# RM1xx-Breakout-min.net
KiCad netlist of a schematic drawn in EAGLE
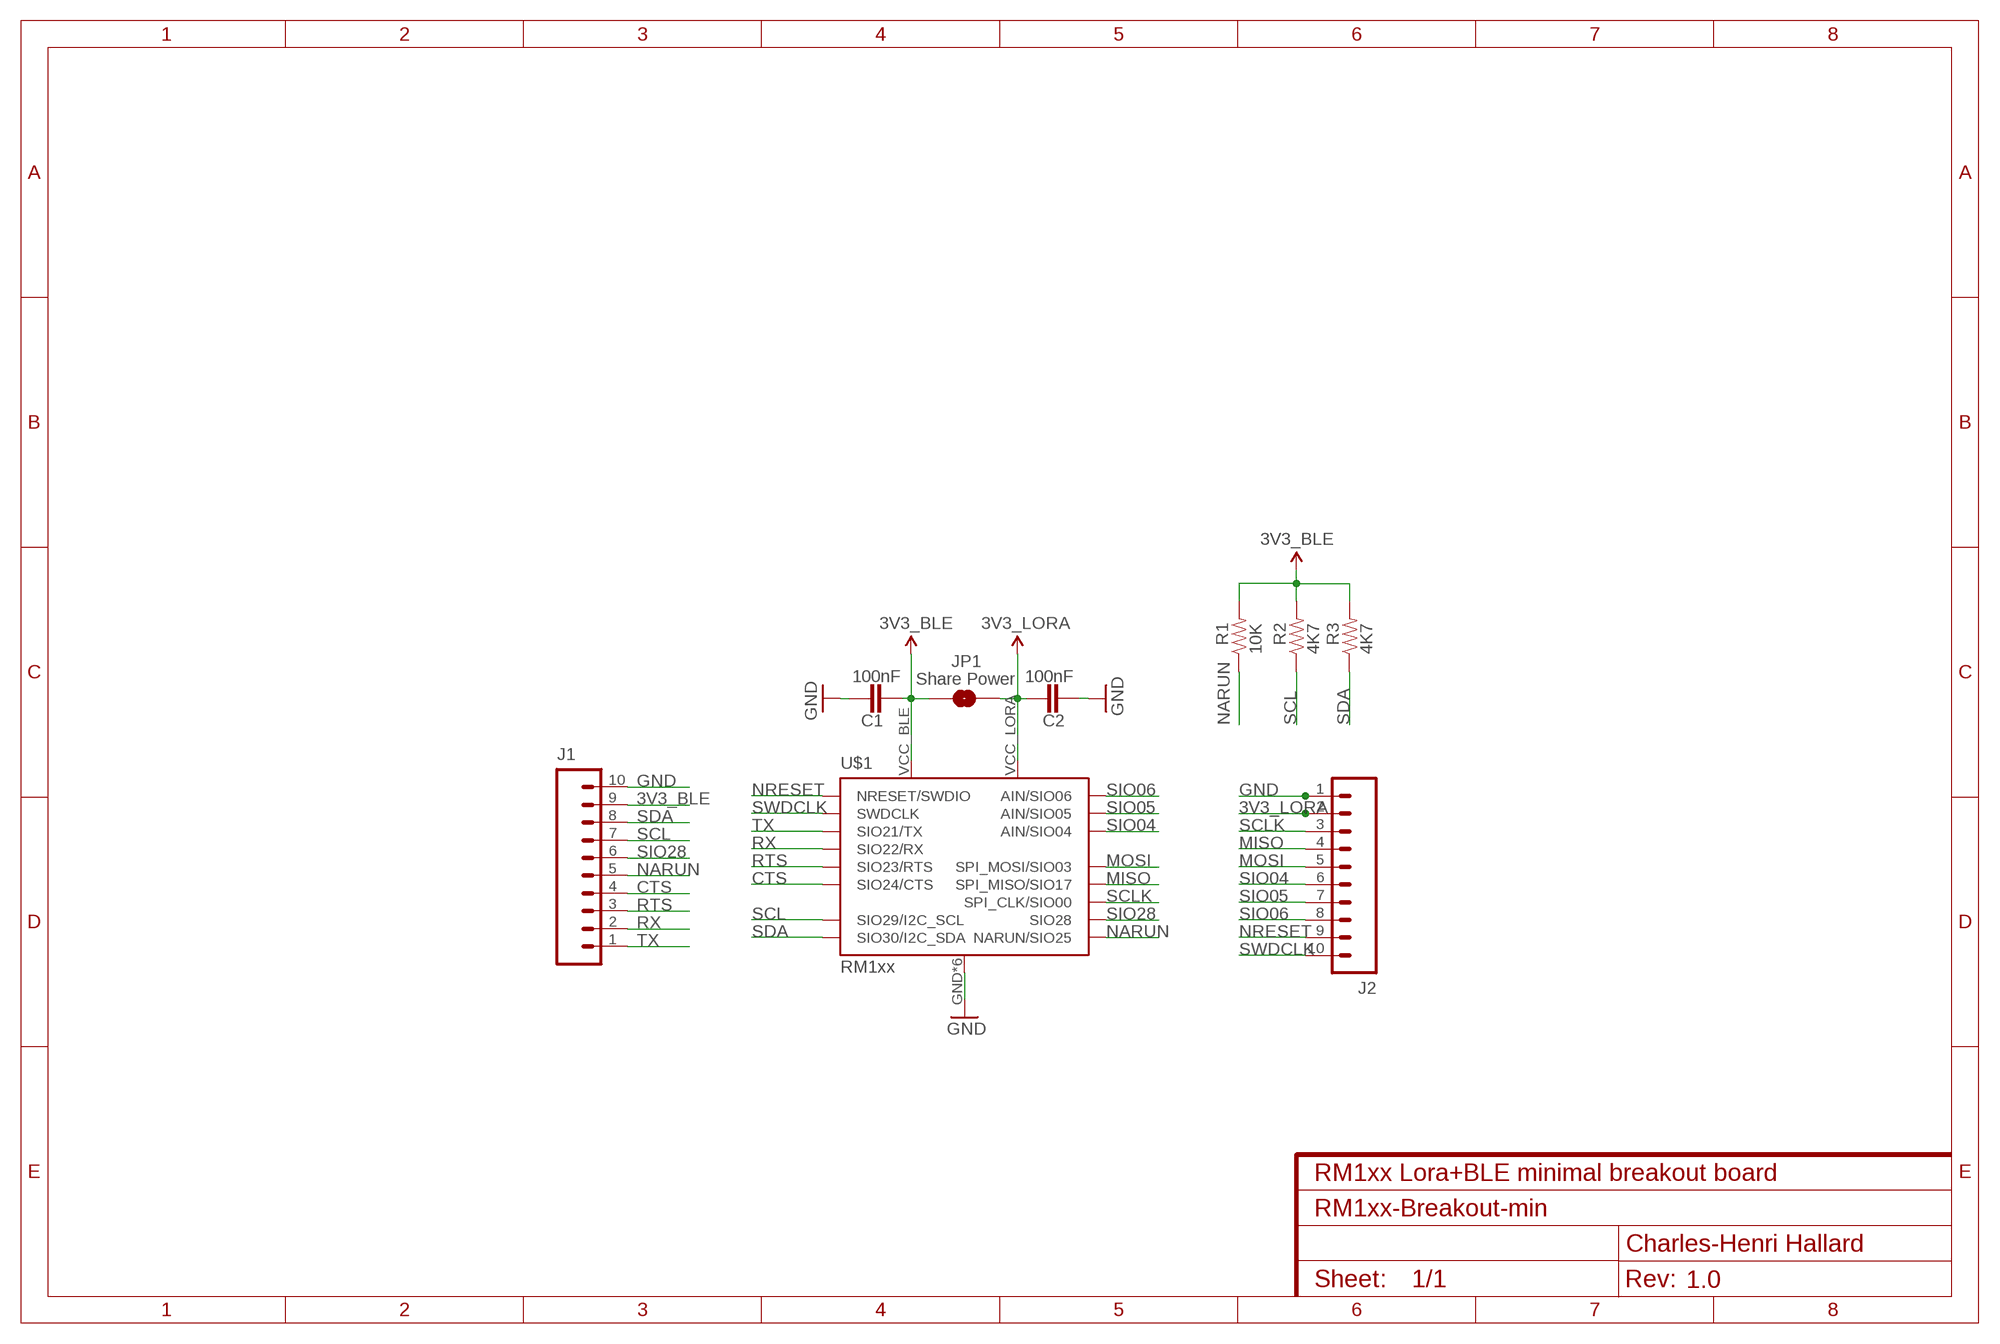
[diagram p0: schematic, sheet 1]

(export (version "E")
  (design (tool "Eeschema 10.0.6"))
  (components
    (comp (ref "C1")
      (value "100nF")
      (footprint "eagle-import:0805-CAP")
      (libsource (lib "eagle-import") (part "CAP0805-CAP"))
    )
    (comp (ref "C2")
      (value "100nF")
      (footprint "eagle-import:0805-CAP")
      (libsource (lib "eagle-import") (part "CAP0805-CAP"))
    )
    (comp (ref "J1")
      (value "M10LOCK")
      (footprint "eagle-import:1X10_LOCK")
      (libsource (lib "eagle-import") (part "M10LOCK"))
    )
    (comp (ref "J2")
      (value "M10LOCK")
      (footprint "eagle-import:1X10_LOCK")
      (libsource (lib "eagle-import") (part "M10LOCK"))
    )
    (comp (ref "JP1")
      (value "Share Power")
      (footprint "eagle-import:PAD-JUMPER-2-NO_YES_SILK")
      (libsource (lib "eagle-import") (part "JUMPER-PAD-2-NOYES_SILK"))
    )
    (comp (ref "R1")
      (value "10K")
      (footprint "eagle-import:0805-RES")
      (libsource (lib "eagle-import") (part "RESISTOR0805-RES"))
    )
    (comp (ref "R2")
      (value "4K7")
      (footprint "eagle-import:0805-RES")
      (libsource (lib "eagle-import") (part "RESISTOR0805-RES"))
    )
    (comp (ref "R3")
      (value "4K7")
      (footprint "eagle-import:0805-RES")
      (libsource (lib "eagle-import") (part "RESISTOR0805-RES"))
    )
    (comp (ref "U$1")
      (value "RM1xx")
      (footprint "eagle-import:RM1XX")
      (libsource (lib "eagle-import") (part "RM1XXSMD"))
    )
  )
  (nets
    (net (code "1") (name "/CTS") (class "Default")
      (node (ref "J1") (pin "4") (pinfunction "4_4") (pintype "passive"))
      (node (ref "U$1") (pin "SIO24") (pinfunction "SIO24/CTS_SIO24") (pintype "bidirectional"))
    )
    (net (code "2") (name "/MISO") (class "Default")
      (node (ref "J2") (pin "4") (pinfunction "4_4") (pintype "passive"))
      (node (ref "U$1") (pin "SIO17") (pinfunction "SPI_MISO/SIO17_SIO17") (pintype "bidirectional"))
    )
    (net (code "3") (name "/MOSI") (class "Default")
      (node (ref "J2") (pin "5") (pinfunction "5_5") (pintype "passive"))
      (node (ref "U$1") (pin "SIO03") (pinfunction "SPI_MOSI/SIO03_SIO03") (pintype "bidirectional"))
    )
    (net (code "4") (name "/NARUN") (class "Default")
      (node (ref "J1") (pin "5") (pinfunction "5_5") (pintype "passive"))
      (node (ref "R1") (pin "1") (pinfunction "1_1") (pintype "passive"))
      (node (ref "U$1") (pin "SIO25") (pinfunction "NARUN/SIO25_SIO25") (pintype "bidirectional"))
    )
    (net (code "5") (name "/NRESET") (class "Default")
      (node (ref "J2") (pin "9") (pinfunction "9_9") (pintype "passive"))
      (node (ref "U$1") (pin "RESET") (pinfunction "NRESET/SWDIO_RESET") (pintype "input"))
    )
    (net (code "6") (name "/RTS") (class "Default")
      (node (ref "J1") (pin "3") (pinfunction "3_3") (pintype "passive"))
      (node (ref "U$1") (pin "SIO23") (pinfunction "SIO23/RTS_SIO23") (pintype "bidirectional"))
    )
    (net (code "7") (name "/RX") (class "Default")
      (node (ref "J1") (pin "2") (pinfunction "2_2") (pintype "passive"))
      (node (ref "U$1") (pin "SIO22") (pinfunction "SIO22/RX_SIO22") (pintype "bidirectional"))
    )
    (net (code "8") (name "/SCL") (class "Default")
      (node (ref "J1") (pin "7") (pinfunction "7_7") (pintype "passive"))
      (node (ref "R2") (pin "1") (pinfunction "1_1") (pintype "passive"))
      (node (ref "U$1") (pin "SIO29") (pinfunction "SIO29/I2C_SCL_SIO29") (pintype "bidirectional"))
    )
    (net (code "9") (name "/SCLK") (class "Default")
      (node (ref "J2") (pin "3") (pinfunction "3_3") (pintype "passive"))
      (node (ref "U$1") (pin "SIO00") (pinfunction "SPI_CLK/SIO00_SIO00") (pintype "bidirectional"))
    )
    (net (code "10") (name "/SDA") (class "Default")
      (node (ref "J1") (pin "8") (pinfunction "8_8") (pintype "passive"))
      (node (ref "R3") (pin "1") (pinfunction "1_1") (pintype "passive"))
      (node (ref "U$1") (pin "SIO30") (pinfunction "SIO30/I2C_SDA_SIO30") (pintype "bidirectional"))
    )
    (net (code "11") (name "/SIO04") (class "Default")
      (node (ref "J2") (pin "6") (pinfunction "6_6") (pintype "passive"))
      (node (ref "U$1") (pin "SIO04") (pinfunction "AIN/SIO04_SIO04") (pintype "bidirectional"))
    )
    (net (code "12") (name "/SIO05") (class "Default")
      (node (ref "J2") (pin "7") (pinfunction "7_7") (pintype "passive"))
      (node (ref "U$1") (pin "SIO05") (pinfunction "AIN/SIO05_SIO05") (pintype "bidirectional"))
    )
    (net (code "13") (name "/SIO06") (class "Default")
      (node (ref "J2") (pin "8") (pinfunction "8_8") (pintype "passive"))
      (node (ref "U$1") (pin "SIO06") (pinfunction "AIN/SIO06_SIO06") (pintype "bidirectional"))
    )
    (net (code "14") (name "/SIO28") (class "Default")
      (node (ref "J1") (pin "6") (pinfunction "6_6") (pintype "passive"))
      (node (ref "U$1") (pin "SIO28") (pinfunction "SIO28_SIO28") (pintype "bidirectional"))
    )
    (net (code "15") (name "/SWDCLK") (class "Default")
      (node (ref "J2") (pin "10") (pinfunction "10_10") (pintype "passive"))
      (node (ref "U$1") (pin "SWDCLK") (pinfunction "SWDCLK_SWDCLK") (pintype "input"))
    )
    (net (code "16") (name "/TX") (class "Default")
      (node (ref "J1") (pin "1") (pinfunction "1_1") (pintype "passive"))
      (node (ref "U$1") (pin "SIO21") (pinfunction "SIO21/TX_SIO21") (pintype "bidirectional"))
    )
    (net (code "17") (name "3V3_BLE") (class "Default")
      (node (ref "C1") (pin "2") (pinfunction "2_2") (pintype "passive"))
      (node (ref "J1") (pin "9") (pinfunction "9_9") (pintype "passive"))
      (node (ref "JP1") (pin "1") (pinfunction "1_1") (pintype "passive"))
      (node (ref "R1") (pin "2") (pinfunction "2_2") (pintype "passive"))
      (node (ref "R2") (pin "2") (pinfunction "2_2") (pintype "passive"))
      (node (ref "R3") (pin "2") (pinfunction "2_2") (pintype "passive"))
      (node (ref "U$1") (pin "VCC_BLE") (pinfunction "VCC_BLE_VCC_BLE") (pintype "power_in"))
    )
    (net (code "18") (name "3V3_LORA") (class "Default")
      (node (ref "C2") (pin "1") (pinfunction "1_1") (pintype "passive"))
      (node (ref "J2") (pin "2") (pinfunction "2_2") (pintype "passive"))
      (node (ref "JP1") (pin "2") (pinfunction "2_2") (pintype "passive"))
      (node (ref "U$1") (pin "VCC_LORA") (pinfunction "VCC_LORA_VCC_LORA") (pintype "power_in"))
    )
    (net (code "19") (name "GND") (class "Default")
      (node (ref "C1") (pin "1") (pinfunction "1_1") (pintype "passive"))
      (node (ref "C2") (pin "2") (pinfunction "2_2") (pintype "passive"))
      (node (ref "J1") (pin "10") (pinfunction "10_10") (pintype "passive"))
      (node (ref "J2") (pin "1") (pinfunction "1_1") (pintype "passive"))
      (node (ref "U$1") (pin "GND") (pinfunction "GND_GND") (pintype "power_in"))
      (node (ref "U$1") (pin "GND1") (pinfunction "GND_GND1") (pintype "power_in"))
      (node (ref "U$1") (pin "GND2") (pinfunction "GND_GND2") (pintype "power_in"))
      (node (ref "U$1") (pin "GND3") (pinfunction "GND_GND3") (pintype "power_in"))
      (node (ref "U$1") (pin "GND4") (pinfunction "GND_GND4") (pintype "power_in"))
      (node (ref "U$1") (pin "GND5") (pinfunction "GND_GND5") (pintype "power_in"))
    )
  )
)
